# PCB_5.net
KiCad netlist of a schematic drawn in EAGLE
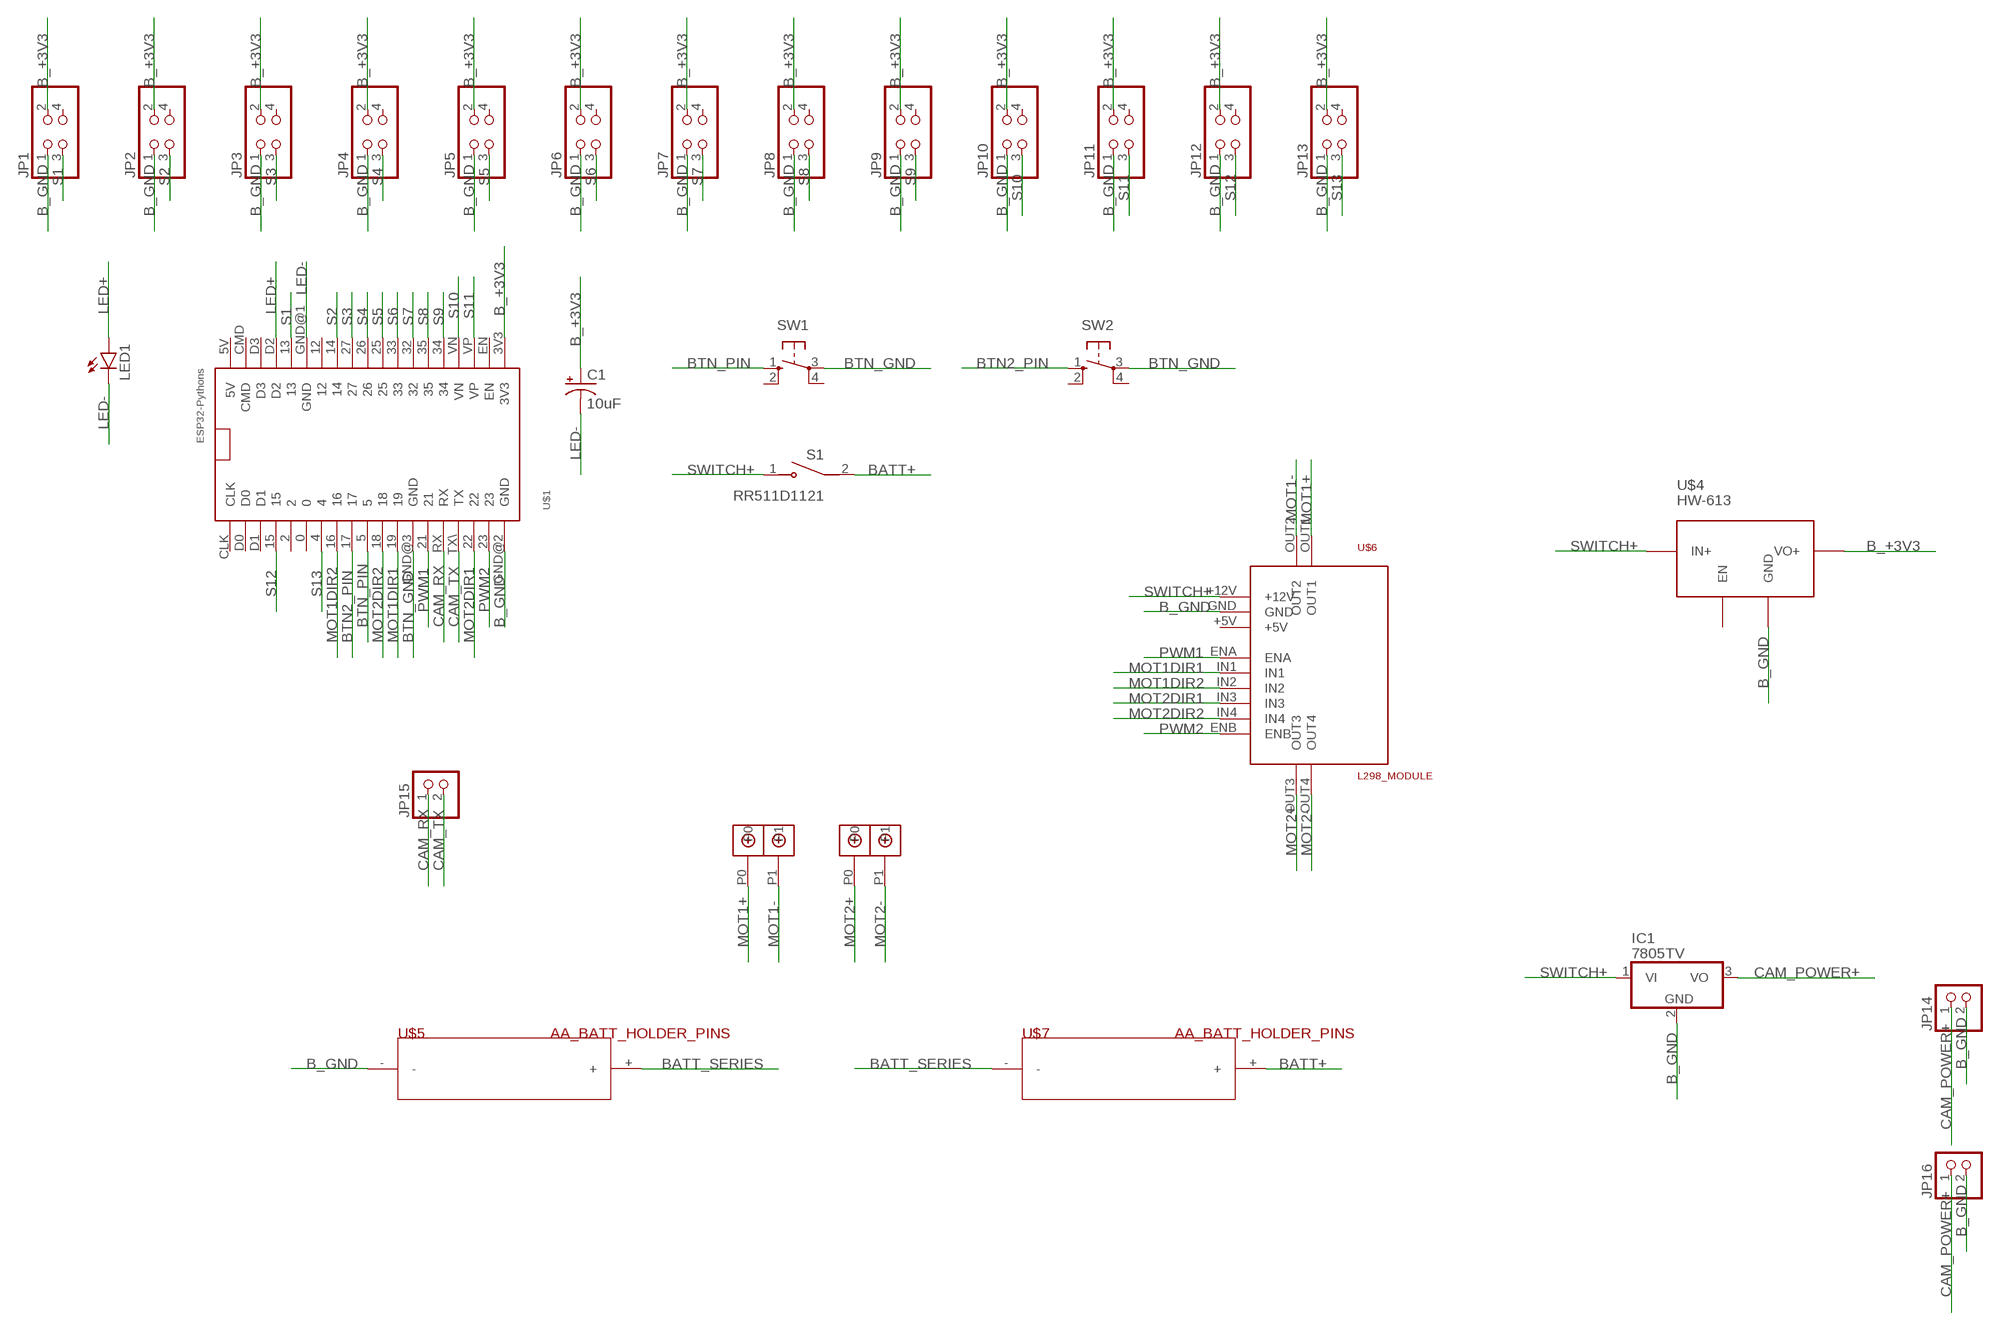
[diagram p0: schematic, sheet 1]

(export (version "E")
  (design (tool "Eeschema 10.0.6"))
  (components
    (comp (ref "C1")
      (value "10uF")
      (footprint "eagle-import:CPOL-RADIAL-2.5MM-5MM")
      (libsource (lib "eagle-import") (part "10UF-POLAR-RADIAL-2.5MM-25V-20%"))
    )
    (comp (ref "IC1")
      (value "7805TV")
      (footprint "eagle-import:TO220V")
      (libsource (lib "eagle-import") (part "78TV05"))
    )
    (comp (ref "JP1")
      (value "PINHD-2X2")
      (footprint "eagle-import:2X02")
      (libsource (lib "eagle-import") (part "PINHD-2X2"))
    )
    (comp (ref "JP2")
      (value "PINHD-2X2")
      (footprint "eagle-import:2X02")
      (libsource (lib "eagle-import") (part "PINHD-2X2"))
    )
    (comp (ref "JP3")
      (value "PINHD-2X2")
      (footprint "eagle-import:2X02")
      (libsource (lib "eagle-import") (part "PINHD-2X2"))
    )
    (comp (ref "JP4")
      (value "PINHD-2X2")
      (footprint "eagle-import:2X02")
      (libsource (lib "eagle-import") (part "PINHD-2X2"))
    )
    (comp (ref "JP5")
      (value "PINHD-2X2")
      (footprint "eagle-import:2X02")
      (libsource (lib "eagle-import") (part "PINHD-2X2"))
    )
    (comp (ref "JP6")
      (value "PINHD-2X2")
      (footprint "eagle-import:2X02")
      (libsource (lib "eagle-import") (part "PINHD-2X2"))
    )
    (comp (ref "JP7")
      (value "PINHD-2X2")
      (footprint "eagle-import:2X02")
      (libsource (lib "eagle-import") (part "PINHD-2X2"))
    )
    (comp (ref "JP8")
      (value "PINHD-2X2")
      (footprint "eagle-import:2X02")
      (libsource (lib "eagle-import") (part "PINHD-2X2"))
    )
    (comp (ref "JP9")
      (value "PINHD-2X2")
      (footprint "eagle-import:2X02")
      (libsource (lib "eagle-import") (part "PINHD-2X2"))
    )
    (comp (ref "JP10")
      (value "PINHD-2X2")
      (footprint "eagle-import:2X02")
      (libsource (lib "eagle-import") (part "PINHD-2X2"))
    )
    (comp (ref "JP11")
      (value "PINHD-2X2")
      (footprint "eagle-import:2X02")
      (libsource (lib "eagle-import") (part "PINHD-2X2"))
    )
    (comp (ref "JP12")
      (value "PINHD-2X2")
      (footprint "eagle-import:2X02")
      (libsource (lib "eagle-import") (part "PINHD-2X2"))
    )
    (comp (ref "JP13")
      (value "PINHD-2X2")
      (footprint "eagle-import:2X02")
      (libsource (lib "eagle-import") (part "PINHD-2X2"))
    )
    (comp (ref "JP14")
      (value "PINHD-1X2")
      (footprint "eagle-import:1X02")
      (libsource (lib "eagle-import") (part "PINHD-1X2"))
    )
    (comp (ref "JP15")
      (value "PINHD-1X2")
      (footprint "eagle-import:1X02")
      (libsource (lib "eagle-import") (part "PINHD-1X2"))
    )
    (comp (ref "JP16")
      (value "PINHD-1X2")
      (footprint "eagle-import:1X02")
      (libsource (lib "eagle-import") (part "PINHD-1X2"))
    )
    (comp (ref "LED1")
      (value "LED5MM")
      (footprint "eagle-import:LED5MM")
      (libsource (lib "eagle-import") (part "LED5MM"))
    )
    (comp (ref "S1")
      (value "RR511D1121")
      (footprint "eagle-import:E-SWITCH_RR511D1121")
      (fields (field (name "MF") "E-Switch"))
      (libsource (lib "eagle-import") (part "RR511D1121"))
    )
    (comp (ref "SW1")
      (value "10-XX")
      (footprint "eagle-import:B3F-10XX")
      (libsource (lib "eagle-import") (part "10-XX"))
    )
    (comp (ref "SW2")
      (value "10-XX")
      (footprint "eagle-import:B3F-10XX")
      (libsource (lib "eagle-import") (part "10-XX"))
    )
    (comp (ref "U$1")
      (value "ESP32DEVKITV1")
      (footprint "eagle-import:ESP32-DEVKITV1")
      (libsource (lib "eagle-import") (part "ESP32DEVKITV1"))
    )
    (comp (ref "U$2")
      (value "DBCONN-1X2")
      (footprint "eagle-import:DBCONN-1X2")
      (libsource (lib "eagle-import") (part "DBCONN-1X2"))
    )
    (comp (ref "U$3")
      (value "DBCONN-1X2")
      (footprint "eagle-import:DBCONN-1X2")
      (libsource (lib "eagle-import") (part "DBCONN-1X2"))
    )
    (comp (ref "U$4")
      (value "HW-613")
      (footprint "eagle-import:HW-613")
      (libsource (lib "eagle-import") (part "HW-613"))
    )
    (comp (ref "U$5")
      (value "AA_BATT_HOLDER_PINS")
      (footprint "eagle-import:AA_BATT_HOLDER_PINS")
      (libsource (lib "eagle-import") (part "AA_BATT_HOLDER_PINS"))
    )
    (comp (ref "U$6")
      (value "L298_MODULE")
      (footprint "eagle-import:L298_MODULE")
      (libsource (lib "eagle-import") (part "L298_MODULE"))
    )
    (comp (ref "U$7")
      (value "AA_BATT_HOLDER_PINS")
      (footprint "eagle-import:AA_BATT_HOLDER_PINS")
      (libsource (lib "eagle-import") (part "AA_BATT_HOLDER_PINS"))
    )
  )
  (nets
    (net (code "1") (name "/BATT+") (class "Default")
      (node (ref "S1") (pin "2") (pinfunction "COM_2") (pintype "passive"))
      (node (ref "U$7") (pin "+") (pinfunction "+_+") (pintype "bidirectional"))
    )
    (net (code "2") (name "/BATT_SERIES") (class "Default")
      (node (ref "U$5") (pin "+") (pinfunction "+_+") (pintype "bidirectional"))
      (node (ref "U$7") (pin "-") (pinfunction "-_-") (pintype "bidirectional"))
    )
    (net (code "3") (name "/BTN2_PIN") (class "Default")
      (node (ref "SW2") (pin "1") (pinfunction "S_1") (pintype "passive"))
      (node (ref "U$1") (pin "17") (pinfunction "17_17") (pintype "bidirectional"))
    )
    (net (code "4") (name "/BTN_GND") (class "Default")
      (node (ref "SW1") (pin "3") (pinfunction "P_3") (pintype "passive"))
      (node (ref "SW2") (pin "3") (pinfunction "P_3") (pintype "passive"))
      (node (ref "U$1") (pin "GND@3") (pinfunction "GND_GND@3") (pintype "bidirectional"))
    )
    (net (code "5") (name "/BTN_PIN") (class "Default")
      (node (ref "SW1") (pin "1") (pinfunction "S_1") (pintype "passive"))
      (node (ref "U$1") (pin "5") (pinfunction "5_5") (pintype "bidirectional"))
    )
    (net (code "6") (name "/B_+3V3") (class "Default")
      (node (ref "C1") (pin "1") (pinfunction "+_1") (pintype "passive"))
      (node (ref "JP1") (pin "2") (pinfunction "2_2") (pintype "passive"))
      (node (ref "JP10") (pin "2") (pinfunction "2_2") (pintype "passive"))
      (node (ref "JP11") (pin "2") (pinfunction "2_2") (pintype "passive"))
      (node (ref "JP12") (pin "2") (pinfunction "2_2") (pintype "passive"))
      (node (ref "JP13") (pin "2") (pinfunction "2_2") (pintype "passive"))
      (node (ref "JP2") (pin "2") (pinfunction "2_2") (pintype "passive"))
      (node (ref "JP3") (pin "2") (pinfunction "2_2") (pintype "passive"))
      (node (ref "JP4") (pin "2") (pinfunction "2_2") (pintype "passive"))
      (node (ref "JP5") (pin "2") (pinfunction "2_2") (pintype "passive"))
      (node (ref "JP6") (pin "2") (pinfunction "2_2") (pintype "passive"))
      (node (ref "JP7") (pin "2") (pinfunction "2_2") (pintype "passive"))
      (node (ref "JP8") (pin "2") (pinfunction "2_2") (pintype "passive"))
      (node (ref "JP9") (pin "2") (pinfunction "2_2") (pintype "passive"))
      (node (ref "U$1") (pin "3V3") (pinfunction "3V3_3V3") (pintype "bidirectional"))
      (node (ref "U$4") (pin "VO+") (pinfunction "VO+_VO+") (pintype "bidirectional"))
    )
    (net (code "7") (name "/B_GND") (class "Default")
      (node (ref "IC1") (pin "2") (pinfunction "GND_2") (pintype "passive"))
      (node (ref "JP1") (pin "1") (pinfunction "1_1") (pintype "passive"))
      (node (ref "JP10") (pin "1") (pinfunction "1_1") (pintype "passive"))
      (node (ref "JP11") (pin "1") (pinfunction "1_1") (pintype "passive"))
      (node (ref "JP12") (pin "1") (pinfunction "1_1") (pintype "passive"))
      (node (ref "JP13") (pin "1") (pinfunction "1_1") (pintype "passive"))
      (node (ref "JP14") (pin "2") (pinfunction "2_2") (pintype "passive"))
      (node (ref "JP16") (pin "2") (pinfunction "2_2") (pintype "passive"))
      (node (ref "JP2") (pin "1") (pinfunction "1_1") (pintype "passive"))
      (node (ref "JP3") (pin "1") (pinfunction "1_1") (pintype "passive"))
      (node (ref "JP4") (pin "1") (pinfunction "1_1") (pintype "passive"))
      (node (ref "JP5") (pin "1") (pinfunction "1_1") (pintype "passive"))
      (node (ref "JP6") (pin "1") (pinfunction "1_1") (pintype "passive"))
      (node (ref "JP7") (pin "1") (pinfunction "1_1") (pintype "passive"))
      (node (ref "JP8") (pin "1") (pinfunction "1_1") (pintype "passive"))
      (node (ref "JP9") (pin "1") (pinfunction "1_1") (pintype "passive"))
      (node (ref "U$1") (pin "GND@2") (pinfunction "GND_GND@2") (pintype "bidirectional"))
      (node (ref "U$4") (pin "GND") (pinfunction "GND_GND") (pintype "bidirectional"))
      (node (ref "U$5") (pin "-") (pinfunction "-_-") (pintype "bidirectional"))
      (node (ref "U$6") (pin "GND") (pinfunction "GND_GND") (pintype "bidirectional"))
    )
    (net (code "8") (name "/CAM_POWER+") (class "Default")
      (node (ref "IC1") (pin "3") (pinfunction "VO_3") (pintype "passive"))
      (node (ref "JP14") (pin "1") (pinfunction "1_1") (pintype "passive"))
      (node (ref "JP16") (pin "1") (pinfunction "1_1") (pintype "passive"))
    )
    (net (code "9") (name "/CAM_RX") (class "Default")
      (node (ref "JP15") (pin "1") (pinfunction "1_1") (pintype "passive"))
      (node (ref "U$1") (pin "RX") (pinfunction "RX_RX") (pintype "bidirectional"))
    )
    (net (code "10") (name "/CAM_TX") (class "Default")
      (node (ref "JP15") (pin "2") (pinfunction "2_2") (pintype "passive"))
      (node (ref "U$1") (pin "TX\\") (pinfunction "TX_TX\\") (pintype "bidirectional"))
    )
    (net (code "11") (name "/LED+") (class "Default")
      (node (ref "LED1") (pin "A") (pinfunction "A_A") (pintype "passive"))
      (node (ref "U$1") (pin "D2") (pinfunction "D2_D2") (pintype "bidirectional"))
    )
    (net (code "12") (name "/LED-") (class "Default")
      (node (ref "C1") (pin "2") (pinfunction "-_2") (pintype "passive"))
      (node (ref "LED1") (pin "K") (pinfunction "C_K") (pintype "passive"))
      (node (ref "U$1") (pin "GND@1") (pinfunction "GND_GND@1") (pintype "bidirectional"))
    )
    (net (code "13") (name "/MOT1+") (class "Default")
      (node (ref "U$2") (pin "P0") (pinfunction "P0_P0") (pintype "bidirectional"))
      (node (ref "U$6") (pin "OUT1") (pinfunction "OUT1_OUT1") (pintype "bidirectional"))
    )
    (net (code "14") (name "/MOT1-") (class "Default")
      (node (ref "U$2") (pin "P1") (pinfunction "P1_P1") (pintype "bidirectional"))
      (node (ref "U$6") (pin "OUT2") (pinfunction "OUT2_OUT2") (pintype "bidirectional"))
    )
    (net (code "15") (name "/MOT1DIR1") (class "Default")
      (node (ref "U$1") (pin "19") (pinfunction "19_19") (pintype "bidirectional"))
      (node (ref "U$6") (pin "IN1") (pinfunction "IN1_IN1") (pintype "bidirectional"))
    )
    (net (code "16") (name "/MOT1DIR2") (class "Default")
      (node (ref "U$1") (pin "16") (pinfunction "16_16") (pintype "bidirectional"))
      (node (ref "U$6") (pin "IN2") (pinfunction "IN2_IN2") (pintype "bidirectional"))
    )
    (net (code "17") (name "/MOT2+") (class "Default")
      (node (ref "U$3") (pin "P0") (pinfunction "P0_P0") (pintype "bidirectional"))
      (node (ref "U$6") (pin "OUT3") (pinfunction "OUT3_OUT3") (pintype "bidirectional"))
    )
    (net (code "18") (name "/MOT2-") (class "Default")
      (node (ref "U$3") (pin "P1") (pinfunction "P1_P1") (pintype "bidirectional"))
      (node (ref "U$6") (pin "OUT4") (pinfunction "OUT4_OUT4") (pintype "bidirectional"))
    )
    (net (code "19") (name "/MOT2DIR1") (class "Default")
      (node (ref "U$1") (pin "22") (pinfunction "22_22") (pintype "bidirectional"))
      (node (ref "U$6") (pin "IN3") (pinfunction "IN3_IN3") (pintype "bidirectional"))
    )
    (net (code "20") (name "/MOT2DIR2") (class "Default")
      (node (ref "U$1") (pin "18") (pinfunction "18_18") (pintype "bidirectional"))
      (node (ref "U$6") (pin "IN4") (pinfunction "IN4_IN4") (pintype "bidirectional"))
    )
    (net (code "21") (name "/PWM1") (class "Default")
      (node (ref "U$1") (pin "21") (pinfunction "21_21") (pintype "bidirectional"))
      (node (ref "U$6") (pin "ENA") (pinfunction "ENA_ENA") (pintype "bidirectional"))
    )
    (net (code "22") (name "/PWM2") (class "Default")
      (node (ref "U$1") (pin "23") (pinfunction "23_23") (pintype "bidirectional"))
      (node (ref "U$6") (pin "ENB") (pinfunction "ENB_ENB") (pintype "bidirectional"))
    )
    (net (code "23") (name "/S1") (class "Default")
      (node (ref "JP1") (pin "3") (pinfunction "3_3") (pintype "passive"))
      (node (ref "U$1") (pin "13") (pinfunction "13_13") (pintype "bidirectional"))
    )
    (net (code "24") (name "/S2") (class "Default")
      (node (ref "JP2") (pin "3") (pinfunction "3_3") (pintype "passive"))
      (node (ref "U$1") (pin "14") (pinfunction "14_14") (pintype "bidirectional"))
    )
    (net (code "25") (name "/S3") (class "Default")
      (node (ref "JP3") (pin "3") (pinfunction "3_3") (pintype "passive"))
      (node (ref "U$1") (pin "27") (pinfunction "27_27") (pintype "bidirectional"))
    )
    (net (code "26") (name "/S4") (class "Default")
      (node (ref "JP4") (pin "3") (pinfunction "3_3") (pintype "passive"))
      (node (ref "U$1") (pin "26") (pinfunction "26_26") (pintype "bidirectional"))
    )
    (net (code "27") (name "/S5") (class "Default")
      (node (ref "JP5") (pin "3") (pinfunction "3_3") (pintype "passive"))
      (node (ref "U$1") (pin "25") (pinfunction "25_25") (pintype "bidirectional"))
    )
    (net (code "28") (name "/S6") (class "Default")
      (node (ref "JP6") (pin "3") (pinfunction "3_3") (pintype "passive"))
      (node (ref "U$1") (pin "33") (pinfunction "33_33") (pintype "bidirectional"))
    )
    (net (code "29") (name "/S7") (class "Default")
      (node (ref "JP7") (pin "3") (pinfunction "3_3") (pintype "passive"))
      (node (ref "U$1") (pin "32") (pinfunction "32_32") (pintype "bidirectional"))
    )
    (net (code "30") (name "/S8") (class "Default")
      (node (ref "JP8") (pin "3") (pinfunction "3_3") (pintype "passive"))
      (node (ref "U$1") (pin "35") (pinfunction "35_35") (pintype "bidirectional"))
    )
    (net (code "31") (name "/S9") (class "Default")
      (node (ref "JP9") (pin "3") (pinfunction "3_3") (pintype "passive"))
      (node (ref "U$1") (pin "34") (pinfunction "34_34") (pintype "bidirectional"))
    )
    (net (code "32") (name "/S10") (class "Default")
      (node (ref "JP10") (pin "3") (pinfunction "3_3") (pintype "passive"))
      (node (ref "U$1") (pin "VN") (pinfunction "VN_VN") (pintype "bidirectional"))
    )
    (net (code "33") (name "/S11") (class "Default")
      (node (ref "JP11") (pin "3") (pinfunction "3_3") (pintype "passive"))
      (node (ref "U$1") (pin "VP") (pinfunction "VP_VP") (pintype "bidirectional"))
    )
    (net (code "34") (name "/S12") (class "Default")
      (node (ref "JP12") (pin "3") (pinfunction "3_3") (pintype "passive"))
      (node (ref "U$1") (pin "15") (pinfunction "15_15") (pintype "bidirectional"))
    )
    (net (code "35") (name "/S13") (class "Default")
      (node (ref "JP13") (pin "3") (pinfunction "3_3") (pintype "passive"))
      (node (ref "U$1") (pin "4") (pinfunction "4_4") (pintype "bidirectional"))
    )
    (net (code "36") (name "/SWITCH+") (class "Default")
      (node (ref "IC1") (pin "1") (pinfunction "VI_1") (pintype "input"))
      (node (ref "S1") (pin "1") (pinfunction "NO_1") (pintype "passive"))
      (node (ref "U$4") (pin "IN+") (pinfunction "IN+_IN+") (pintype "bidirectional"))
      (node (ref "U$6") (pin "+12V") (pinfunction "+12V_+12V") (pintype "bidirectional"))
    )
    (net (code "37") (name "unconnected-(JP1-Pad4)") (class "Default")
      (node (ref "JP1") (pin "4") (pinfunction "4_4") (pintype "passive"))
    )
    (net (code "38") (name "unconnected-(JP2-Pad4)") (class "Default")
      (node (ref "JP2") (pin "4") (pinfunction "4_4") (pintype "passive"))
    )
    (net (code "39") (name "unconnected-(JP3-Pad4)") (class "Default")
      (node (ref "JP3") (pin "4") (pinfunction "4_4") (pintype "passive"))
    )
    (net (code "40") (name "unconnected-(JP4-Pad4)") (class "Default")
      (node (ref "JP4") (pin "4") (pinfunction "4_4") (pintype "passive"))
    )
    (net (code "41") (name "unconnected-(JP5-Pad4)") (class "Default")
      (node (ref "JP5") (pin "4") (pinfunction "4_4") (pintype "passive"))
    )
    (net (code "42") (name "unconnected-(JP6-Pad4)") (class "Default")
      (node (ref "JP6") (pin "4") (pinfunction "4_4") (pintype "passive"))
    )
    (net (code "43") (name "unconnected-(JP7-Pad4)") (class "Default")
      (node (ref "JP7") (pin "4") (pinfunction "4_4") (pintype "passive"))
    )
    (net (code "44") (name "unconnected-(JP8-Pad4)") (class "Default")
      (node (ref "JP8") (pin "4") (pinfunction "4_4") (pintype "passive"))
    )
    (net (code "45") (name "unconnected-(JP9-Pad4)") (class "Default")
      (node (ref "JP9") (pin "4") (pinfunction "4_4") (pintype "passive"))
    )
    (net (code "46") (name "unconnected-(JP10-Pad4)") (class "Default")
      (node (ref "JP10") (pin "4") (pinfunction "4_4") (pintype "passive"))
    )
    (net (code "47") (name "unconnected-(JP11-Pad4)") (class "Default")
      (node (ref "JP11") (pin "4") (pinfunction "4_4") (pintype "passive"))
    )
    (net (code "48") (name "unconnected-(JP12-Pad4)") (class "Default")
      (node (ref "JP12") (pin "4") (pinfunction "4_4") (pintype "passive"))
    )
    (net (code "49") (name "unconnected-(JP13-Pad4)") (class "Default")
      (node (ref "JP13") (pin "4") (pinfunction "4_4") (pintype "passive"))
    )
    (net (code "50") (name "unconnected-(SW1-P1-Pad4)") (class "Default")
      (node (ref "SW1") (pin "4") (pinfunction "P1_4") (pintype "passive"))
    )
    (net (code "51") (name "unconnected-(SW1-S1-Pad2)") (class "Default")
      (node (ref "SW1") (pin "2") (pinfunction "S1_2") (pintype "passive"))
    )
    (net (code "52") (name "unconnected-(SW2-P1-Pad4)") (class "Default")
      (node (ref "SW2") (pin "4") (pinfunction "P1_4") (pintype "passive"))
    )
    (net (code "53") (name "unconnected-(SW2-S1-Pad2)") (class "Default")
      (node (ref "SW2") (pin "2") (pinfunction "S1_2") (pintype "passive"))
    )
    (net (code "54") (name "unconnected-(U$1-Pad0)") (class "Default")
      (node (ref "U$1") (pin "0") (pinfunction "0_0") (pintype "bidirectional"))
    )
    (net (code "55") (name "unconnected-(U$1-Pad2)") (class "Default")
      (node (ref "U$1") (pin "2") (pinfunction "2_2") (pintype "bidirectional"))
    )
    (net (code "56") (name "unconnected-(U$1-Pad5V)") (class "Default")
      (node (ref "U$1") (pin "5V") (pinfunction "5V_5V") (pintype "bidirectional"))
    )
    (net (code "57") (name "unconnected-(U$1-Pad12)") (class "Default")
      (node (ref "U$1") (pin "12") (pinfunction "12_12") (pintype "bidirectional"))
    )
    (net (code "58") (name "unconnected-(U$1-PadCLK)") (class "Default")
      (node (ref "U$1") (pin "CLK") (pinfunction "CLK_CLK") (pintype "bidirectional"))
    )
    (net (code "59") (name "unconnected-(U$1-PadCMD)") (class "Default")
      (node (ref "U$1") (pin "CMD") (pinfunction "CMD_CMD") (pintype "bidirectional"))
    )
    (net (code "60") (name "unconnected-(U$1-PadD0)") (class "Default")
      (node (ref "U$1") (pin "D0") (pinfunction "D0_D0") (pintype "bidirectional"))
    )
    (net (code "61") (name "unconnected-(U$1-PadD1)") (class "Default")
      (node (ref "U$1") (pin "D1") (pinfunction "D1_D1") (pintype "bidirectional"))
    )
    (net (code "62") (name "unconnected-(U$1-PadD3)") (class "Default")
      (node (ref "U$1") (pin "D3") (pinfunction "D3_D3") (pintype "bidirectional"))
    )
    (net (code "63") (name "unconnected-(U$1-PadEN)") (class "Default")
      (node (ref "U$1") (pin "EN") (pinfunction "EN_EN") (pintype "bidirectional"))
    )
    (net (code "64") (name "unconnected-(U$4-PadEN)") (class "Default")
      (node (ref "U$4") (pin "EN") (pinfunction "EN_EN") (pintype "bidirectional"))
    )
    (net (code "65") (name "unconnected-(U$6-Pad+5V)") (class "Default")
      (node (ref "U$6") (pin "+5V") (pinfunction "+5V_+5V") (pintype "bidirectional"))
    )
  )
)
